# M221X.net
KiCad netlist of a schematic drawn in EAGLE
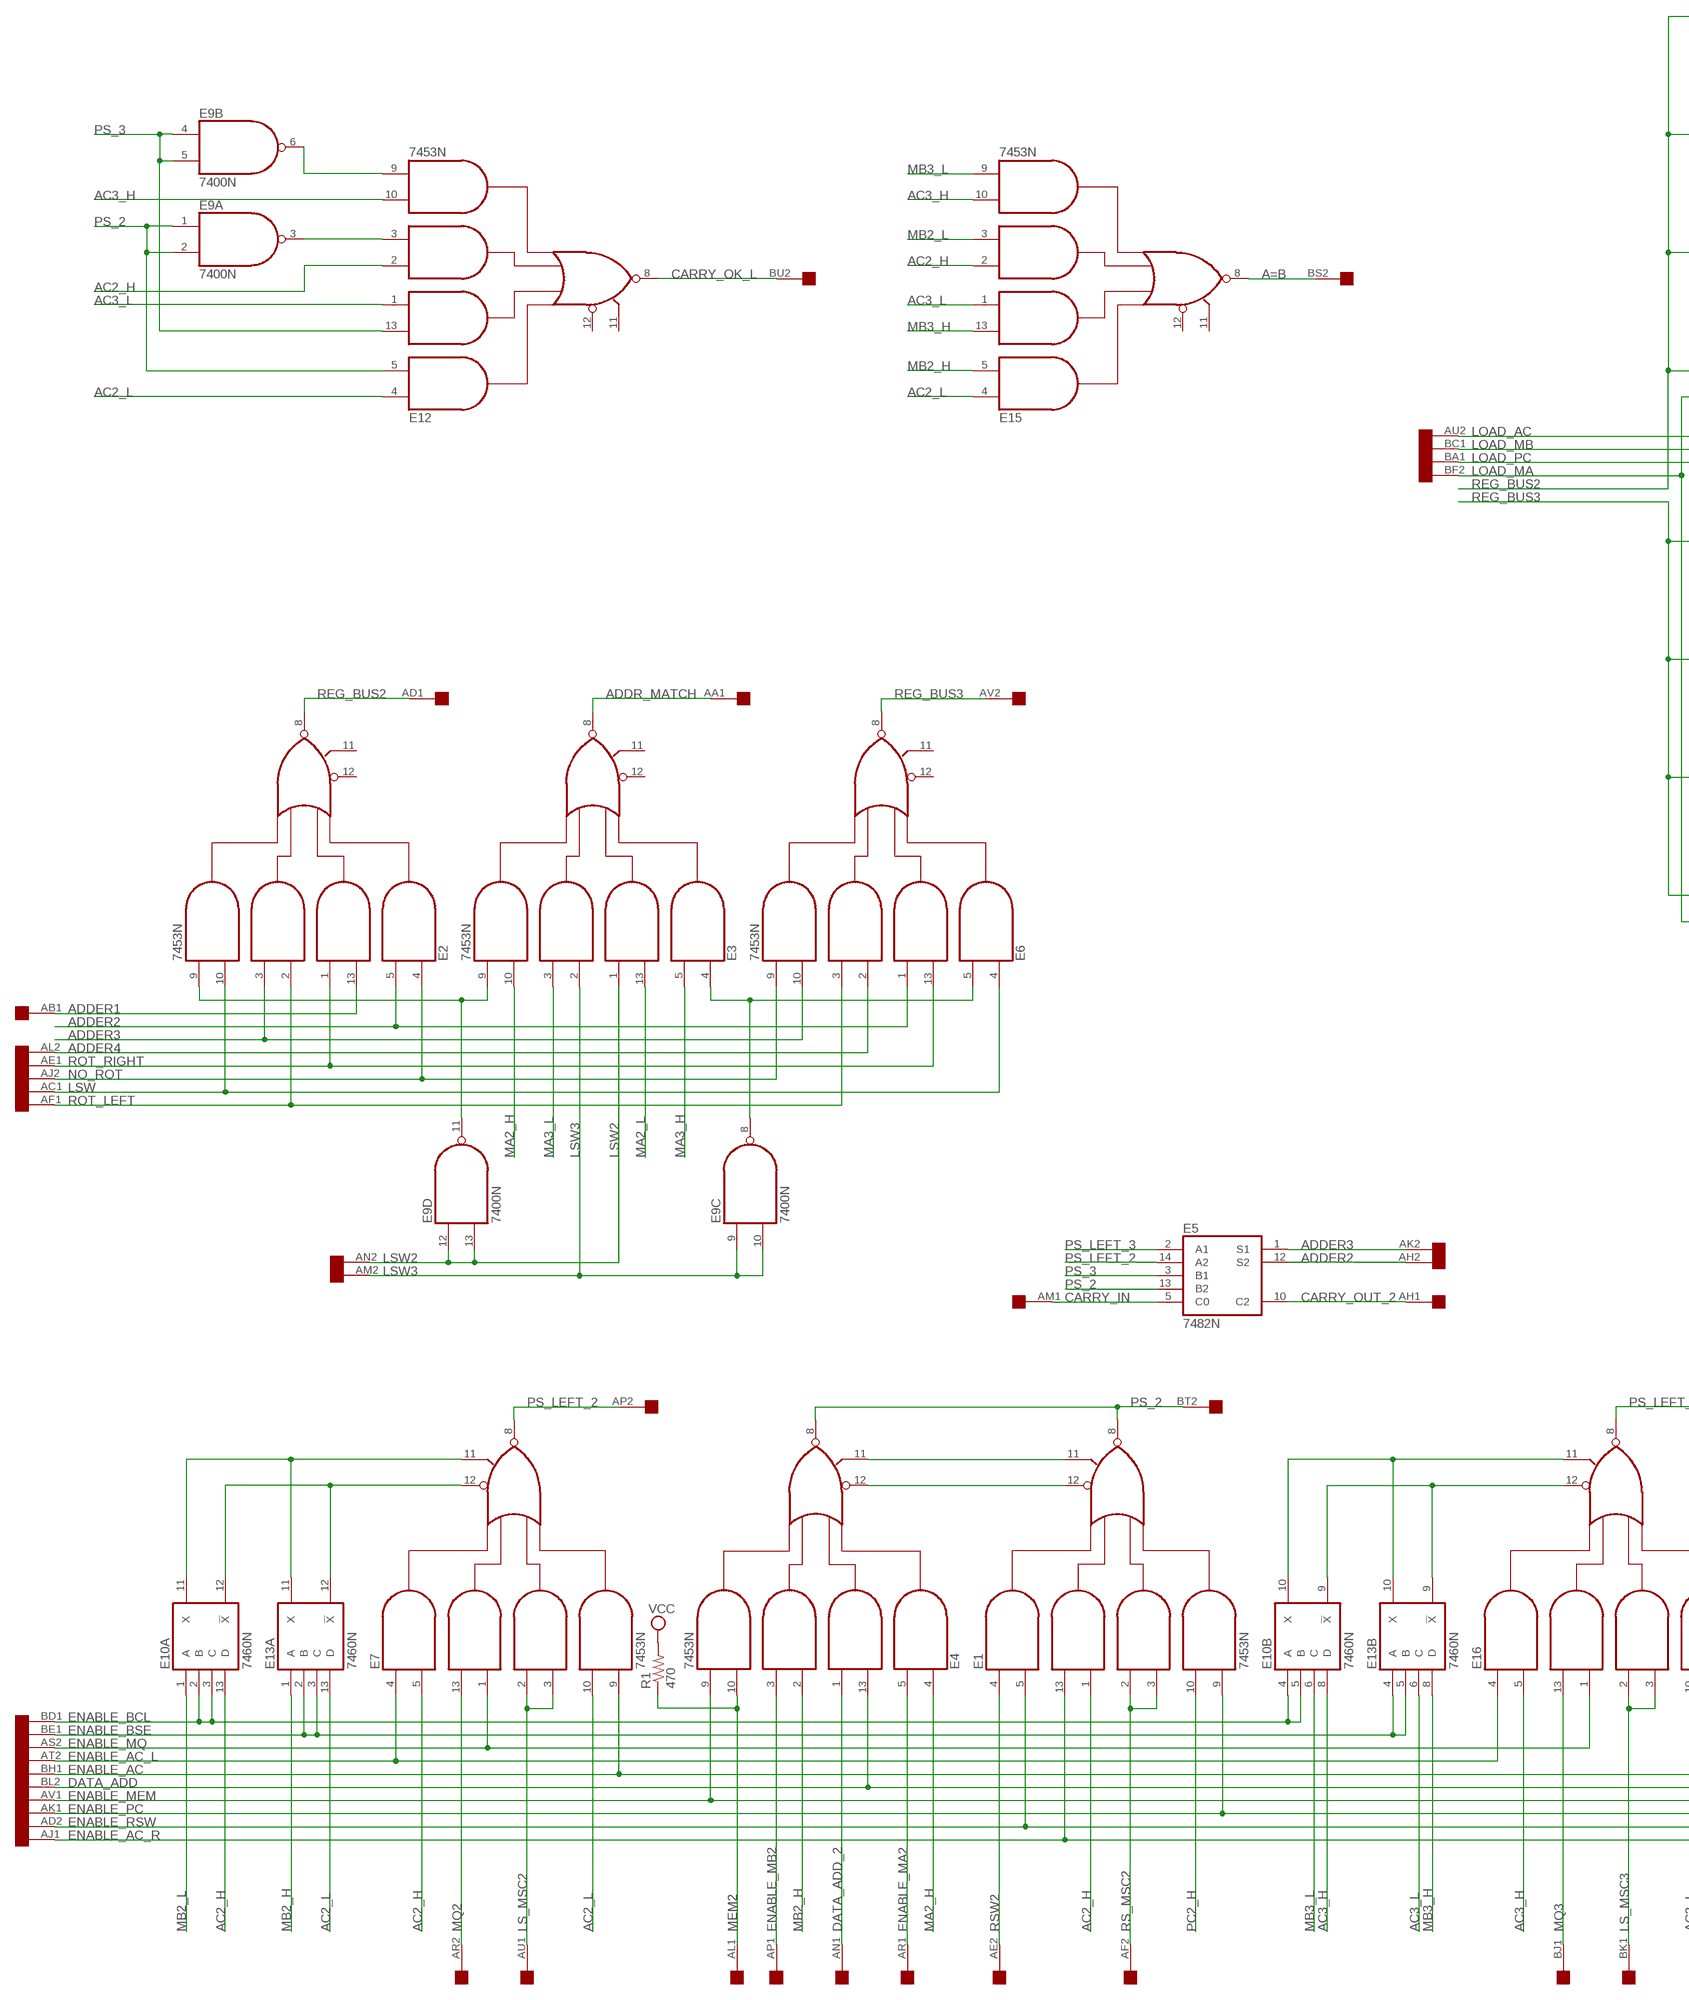
[diagram p0: schematic, sheet 1, part 1 of 2]
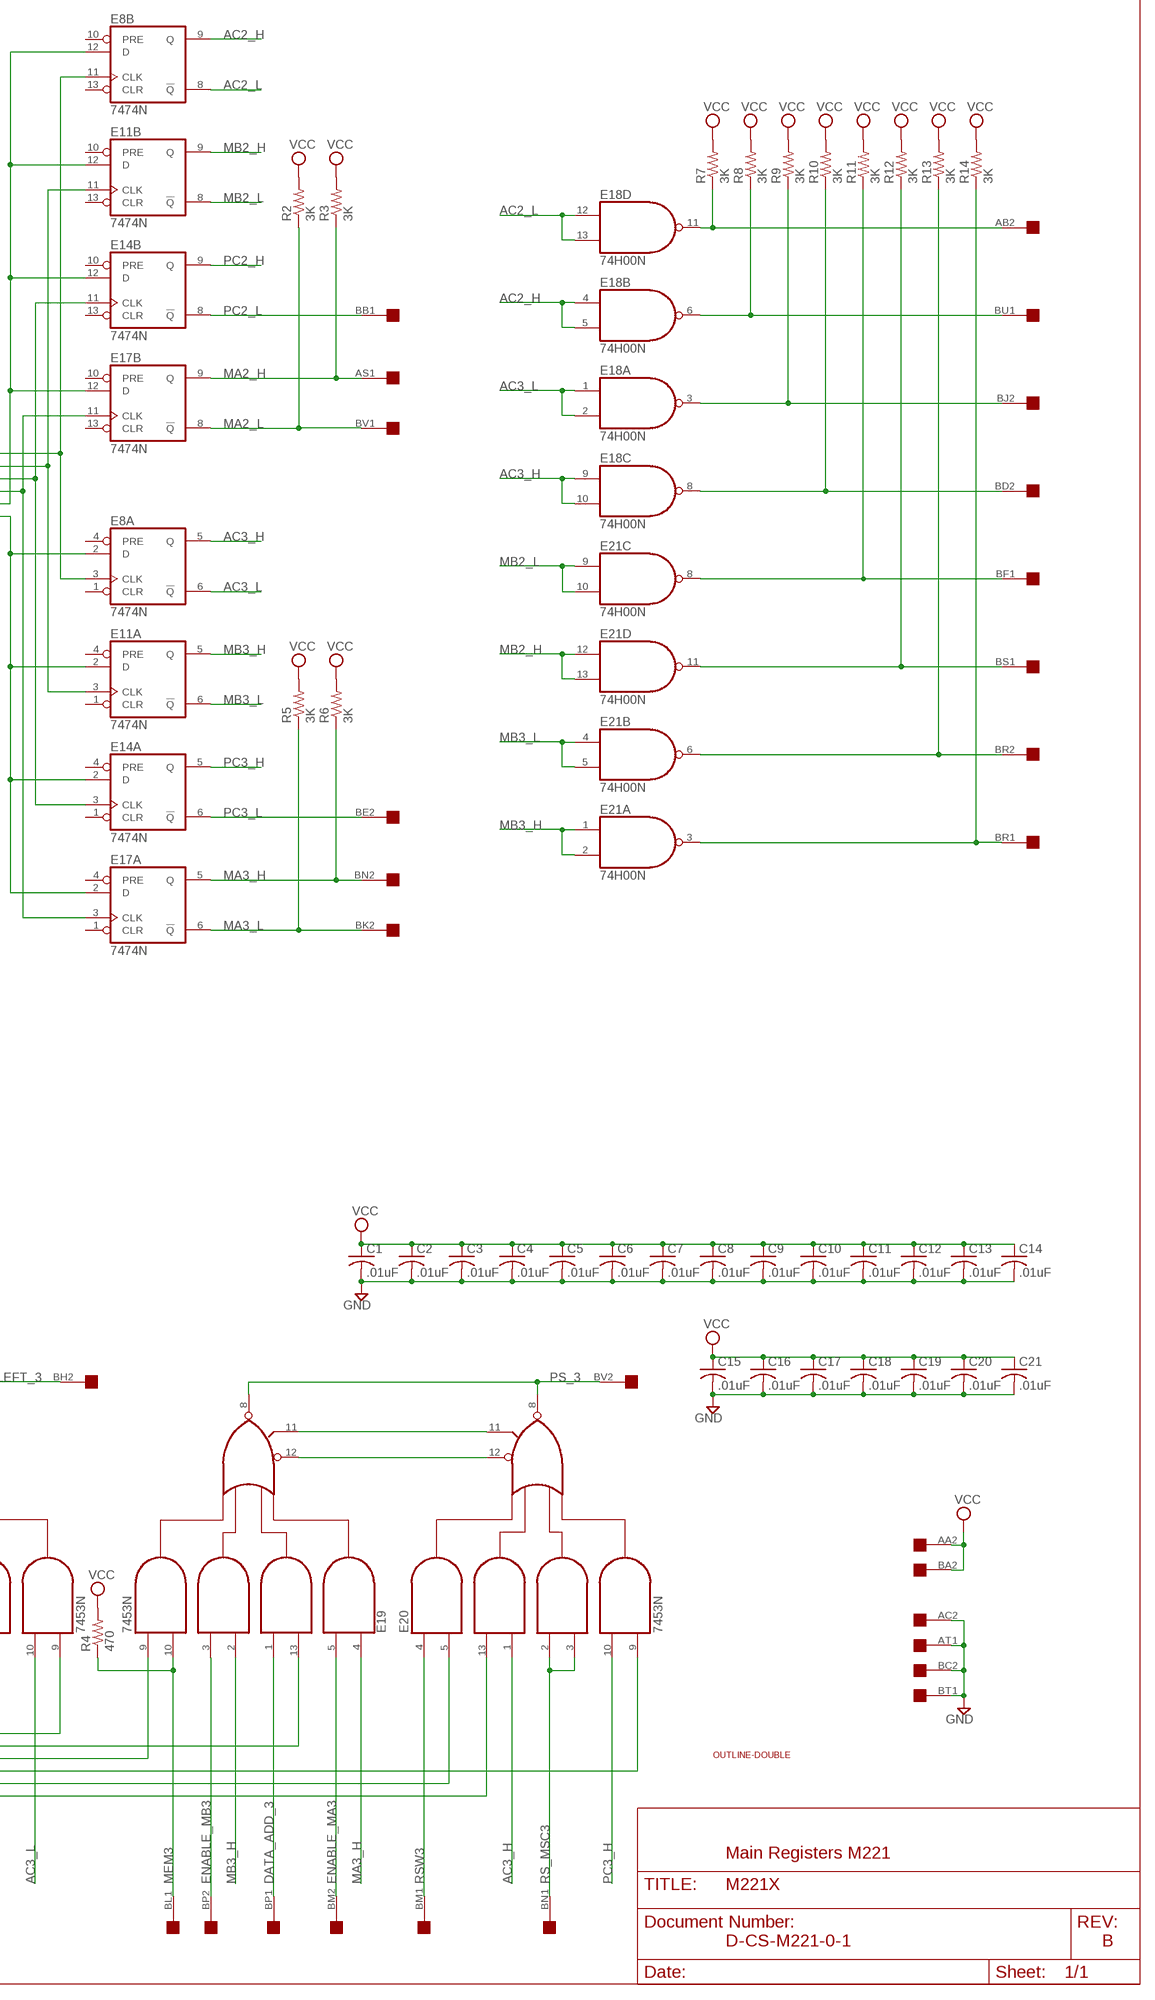
[diagram p1: schematic, sheet 1, part 2 of 2]

(export (version "E")
  (design (tool "Eeschema 10.0.6"))
  (components
    (comp (ref "C1")
      (value ".01uF")
      (footprint "eagle-import:C050-025X075")
      (libsource (lib "eagle-import") (part "C-US050-025X075"))
    )
    (comp (ref "C2")
      (value ".01uF")
      (footprint "eagle-import:C050-025X075")
      (libsource (lib "eagle-import") (part "C-US050-025X075"))
    )
    (comp (ref "C3")
      (value ".01uF")
      (footprint "eagle-import:C050-025X075")
      (libsource (lib "eagle-import") (part "C-US050-025X075"))
    )
    (comp (ref "C4")
      (value ".01uF")
      (footprint "eagle-import:C050-025X075")
      (libsource (lib "eagle-import") (part "C-US050-025X075"))
    )
    (comp (ref "C5")
      (value ".01uF")
      (footprint "eagle-import:C050-025X075")
      (libsource (lib "eagle-import") (part "C-US050-025X075"))
    )
    (comp (ref "C6")
      (value ".01uF")
      (footprint "eagle-import:C050-025X075")
      (libsource (lib "eagle-import") (part "C-US050-025X075"))
    )
    (comp (ref "C7")
      (value ".01uF")
      (footprint "eagle-import:C050-025X075")
      (libsource (lib "eagle-import") (part "C-US050-025X075"))
    )
    (comp (ref "C8")
      (value ".01uF")
      (footprint "eagle-import:C050-025X075")
      (libsource (lib "eagle-import") (part "C-US050-025X075"))
    )
    (comp (ref "C9")
      (value ".01uF")
      (footprint "eagle-import:C050-025X075")
      (libsource (lib "eagle-import") (part "C-US050-025X075"))
    )
    (comp (ref "C10")
      (value ".01uF")
      (footprint "eagle-import:C050-025X075")
      (libsource (lib "eagle-import") (part "C-US050-025X075"))
    )
    (comp (ref "C11")
      (value ".01uF")
      (footprint "eagle-import:C050-025X075")
      (libsource (lib "eagle-import") (part "C-US050-025X075"))
    )
    (comp (ref "C12")
      (value ".01uF")
      (footprint "eagle-import:C050-025X075")
      (libsource (lib "eagle-import") (part "C-US050-025X075"))
    )
    (comp (ref "C13")
      (value ".01uF")
      (footprint "eagle-import:C050-025X075")
      (libsource (lib "eagle-import") (part "C-US050-025X075"))
    )
    (comp (ref "C14")
      (value ".01uF")
      (footprint "eagle-import:C050-025X075")
      (libsource (lib "eagle-import") (part "C-US050-025X075"))
    )
    (comp (ref "C15")
      (value ".01uF")
      (footprint "eagle-import:C050-025X075")
      (libsource (lib "eagle-import") (part "C-US050-025X075"))
    )
    (comp (ref "C16")
      (value ".01uF")
      (footprint "eagle-import:C050-025X075")
      (libsource (lib "eagle-import") (part "C-US050-025X075"))
    )
    (comp (ref "C17")
      (value ".01uF")
      (footprint "eagle-import:C050-025X075")
      (libsource (lib "eagle-import") (part "C-US050-025X075"))
    )
    (comp (ref "C18")
      (value ".01uF")
      (footprint "eagle-import:C050-025X075")
      (libsource (lib "eagle-import") (part "C-US050-025X075"))
    )
    (comp (ref "C19")
      (value ".01uF")
      (footprint "eagle-import:C050-025X075")
      (libsource (lib "eagle-import") (part "C-US050-025X075"))
    )
    (comp (ref "C20")
      (value ".01uF")
      (footprint "eagle-import:C050-025X075")
      (libsource (lib "eagle-import") (part "C-US050-025X075"))
    )
    (comp (ref "C21")
      (value ".01uF")
      (footprint "eagle-import:C050-025X075")
      (libsource (lib "eagle-import") (part "C-US050-025X075"))
    )
    (comp (ref "E1")
      (value "7453N")
      (footprint "eagle-import:DIL14")
      (libsource (lib "eagle-import") (part "7453N"))
    )
    (comp (ref "E2")
      (value "7453N")
      (footprint "eagle-import:DIL14")
      (libsource (lib "eagle-import") (part "7453N"))
    )
    (comp (ref "E3")
      (value "7453N")
      (footprint "eagle-import:DIL14")
      (libsource (lib "eagle-import") (part "7453N"))
    )
    (comp (ref "E4")
      (value "7453N")
      (footprint "eagle-import:DIL14")
      (libsource (lib "eagle-import") (part "7453N"))
    )
    (comp (ref "E5")
      (value "7482N")
      (footprint "eagle-import:DIL14")
      (libsource (lib "eagle-import") (part "7482N"))
    )
    (comp (ref "E6")
      (value "7453N")
      (footprint "eagle-import:DIL14")
      (libsource (lib "eagle-import") (part "7453N"))
    )
    (comp (ref "E7")
      (value "7453N")
      (footprint "eagle-import:DIL14")
      (libsource (lib "eagle-import") (part "7453N"))
    )
    (comp (ref "E8")
      (value "7474N")
      (footprint "eagle-import:DIL14")
      (libsource (lib "eagle-import") (part "7474NS"))
    )
    (comp (ref "E9")
      (value "7400N")
      (footprint "eagle-import:DIL14")
      (libsource (lib "eagle-import") (part "7400N"))
    )
    (comp (ref "E10")
      (value "7460N")
      (footprint "eagle-import:DIL14")
      (libsource (lib "eagle-import") (part "7460N"))
    )
    (comp (ref "E11")
      (value "7474N")
      (footprint "eagle-import:DIL14")
      (libsource (lib "eagle-import") (part "7474NS"))
    )
    (comp (ref "E12")
      (value "7453N")
      (footprint "eagle-import:DIL14")
      (libsource (lib "eagle-import") (part "7453N"))
    )
    (comp (ref "E13")
      (value "7460N")
      (footprint "eagle-import:DIL14")
      (libsource (lib "eagle-import") (part "7460N"))
    )
    (comp (ref "E14")
      (value "7474N")
      (footprint "eagle-import:DIL14")
      (libsource (lib "eagle-import") (part "7474NS"))
    )
    (comp (ref "E15")
      (value "7453N")
      (footprint "eagle-import:DIL14")
      (libsource (lib "eagle-import") (part "7453N"))
    )
    (comp (ref "E16")
      (value "7453N")
      (footprint "eagle-import:DIL14")
      (libsource (lib "eagle-import") (part "7453N"))
    )
    (comp (ref "E17")
      (value "7474N")
      (footprint "eagle-import:DIL14")
      (libsource (lib "eagle-import") (part "7474NS"))
    )
    (comp (ref "E18")
      (value "74H00N")
      (footprint "eagle-import:DIL14")
      (libsource (lib "eagle-import") (part "7400N"))
    )
    (comp (ref "E19")
      (value "7453N")
      (footprint "eagle-import:DIL14")
      (libsource (lib "eagle-import") (part "7453N"))
    )
    (comp (ref "E20")
      (value "7453N")
      (footprint "eagle-import:DIL14")
      (libsource (lib "eagle-import") (part "7453N"))
    )
    (comp (ref "E21")
      (value "74H00N")
      (footprint "eagle-import:DIL14")
      (libsource (lib "eagle-import") (part "7400N"))
    )
    (comp (ref "R1")
      (value "470")
      (footprint "eagle-import:0207_10")
      (libsource (lib "eagle-import") (part "R-US_0207/10"))
    )
    (comp (ref "R2")
      (value "3K")
      (footprint "eagle-import:0207_10")
      (libsource (lib "eagle-import") (part "R-US_0207/10"))
    )
    (comp (ref "R3")
      (value "3K")
      (footprint "eagle-import:0207_10")
      (libsource (lib "eagle-import") (part "R-US_0207/10"))
    )
    (comp (ref "R4")
      (value "470")
      (footprint "eagle-import:0207_10")
      (libsource (lib "eagle-import") (part "R-US_0207/10"))
    )
    (comp (ref "R5")
      (value "3K")
      (footprint "eagle-import:0207_10")
      (libsource (lib "eagle-import") (part "R-US_0207/10"))
    )
    (comp (ref "R6")
      (value "3K")
      (footprint "eagle-import:0207_10")
      (libsource (lib "eagle-import") (part "R-US_0207/10"))
    )
    (comp (ref "R7")
      (value "3K")
      (footprint "eagle-import:0207_10")
      (libsource (lib "eagle-import") (part "R-US_0207/10"))
    )
    (comp (ref "R8")
      (value "3K")
      (footprint "eagle-import:0207_10")
      (libsource (lib "eagle-import") (part "R-US_0207/10"))
    )
    (comp (ref "R9")
      (value "3K")
      (footprint "eagle-import:0207_10")
      (libsource (lib "eagle-import") (part "R-US_0207/10"))
    )
    (comp (ref "R10")
      (value "3K")
      (footprint "eagle-import:0207_10")
      (libsource (lib "eagle-import") (part "R-US_0207/10"))
    )
    (comp (ref "R11")
      (value "3K")
      (footprint "eagle-import:0207_10")
      (libsource (lib "eagle-import") (part "R-US_0207/10"))
    )
    (comp (ref "R12")
      (value "3K")
      (footprint "eagle-import:0207_10")
      (libsource (lib "eagle-import") (part "R-US_0207/10"))
    )
    (comp (ref "R13")
      (value "3K")
      (footprint "eagle-import:0207_10")
      (libsource (lib "eagle-import") (part "R-US_0207/10"))
    )
    (comp (ref "R14")
      (value "3K")
      (footprint "eagle-import:0207_10")
      (libsource (lib "eagle-import") (part "R-US_0207/10"))
    )
    (comp (ref "U$1")
      (value "DOUBLE")
      (footprint "eagle-import:EDGE-CON4")
      (libsource (lib "eagle-import") (part "DOUBLE"))
    )
    (comp (ref "U$2")
      (value "OUTLINE-DOUBLE")
      (footprint "eagle-import:DOUBLE")
      (libsource (lib "eagle-import") (part "OUTLINE-DOUBLE"))
    )
  )
  (nets
    (net (code "1") (name "/A=B") (class "Default")
      (node (ref "E15") (pin "8") (pinfunction "O_8") (pintype "output"))
      (node (ref "U$1") (pin "BS2") (pinfunction "1_BS2") (pintype "bidirectional"))
    )
    (net (code "2") (name "/AC2_H") (class "Default")
      (node (ref "E1") (pin "1") (pinfunction "I4_1") (pintype "input"))
      (node (ref "E10") (pin "13") (pinfunction "D_13") (pintype "input"))
      (node (ref "E12") (pin "2") (pinfunction "I5_2") (pintype "input"))
      (node (ref "E15") (pin "2") (pinfunction "I5_2") (pintype "input"))
      (node (ref "E18") (pin "4") (pinfunction "I0_4") (pintype "input"))
      (node (ref "E18") (pin "5") (pinfunction "I1_5") (pintype "input"))
      (node (ref "E7") (pin "5") (pinfunction "I2_5") (pintype "input"))
      (node (ref "E8") (pin "9") (pinfunction "Q_9") (pintype "output"))
    )
    (net (code "3") (name "/AC2_L") (class "Default")
      (node (ref "E12") (pin "4") (pinfunction "I1_4") (pintype "input"))
      (node (ref "E13") (pin "13") (pinfunction "D_13") (pintype "input"))
      (node (ref "E15") (pin "4") (pinfunction "I1_4") (pintype "input"))
      (node (ref "E18") (pin "12") (pinfunction "I0_12") (pintype "input"))
      (node (ref "E18") (pin "13") (pinfunction "I1_13") (pintype "input"))
      (node (ref "E7") (pin "10") (pinfunction "I7_10") (pintype "input"))
      (node (ref "E8") (pin "8") (pinfunction "~{Q}_8") (pintype "output"))
    )
    (net (code "4") (name "/AC3_H") (class "Default")
      (node (ref "E10") (pin "8") (pinfunction "D_8") (pintype "input"))
      (node (ref "E12") (pin "10") (pinfunction "I7_10") (pintype "input"))
      (node (ref "E15") (pin "10") (pinfunction "I7_10") (pintype "input"))
      (node (ref "E16") (pin "5") (pinfunction "I2_5") (pintype "input"))
      (node (ref "E18") (pin "10") (pinfunction "I1_10") (pintype "input"))
      (node (ref "E18") (pin "9") (pinfunction "I0_9") (pintype "input"))
      (node (ref "E20") (pin "1") (pinfunction "I4_1") (pintype "input"))
      (node (ref "E8") (pin "5") (pinfunction "Q_5") (pintype "output"))
    )
    (net (code "5") (name "/AC3_L") (class "Default")
      (node (ref "E12") (pin "1") (pinfunction "I4_1") (pintype "input"))
      (node (ref "E13") (pin "6") (pinfunction "C_6") (pintype "input"))
      (node (ref "E15") (pin "1") (pinfunction "I4_1") (pintype "input"))
      (node (ref "E16") (pin "10") (pinfunction "I7_10") (pintype "input"))
      (node (ref "E18") (pin "1") (pinfunction "I0_1") (pintype "input"))
      (node (ref "E18") (pin "2") (pinfunction "I1_2") (pintype "input"))
      (node (ref "E8") (pin "6") (pinfunction "~{Q}_6") (pintype "output"))
    )
    (net (code "6") (name "/ADDER1") (class "Default")
      (node (ref "E2") (pin "13") (pinfunction "I3_13") (pintype "input"))
      (node (ref "U$1") (pin "AB1") (pinfunction "1_AB1") (pintype "bidirectional"))
    )
    (net (code "7") (name "/ADDER2") (class "Default")
      (node (ref "E2") (pin "5") (pinfunction "I2_5") (pintype "input"))
      (node (ref "E5") (pin "12") (pinfunction "S2_12") (pintype "output"))
      (node (ref "E6") (pin "1") (pinfunction "I4_1") (pintype "input"))
      (node (ref "U$1") (pin "AH2") (pinfunction "1_AH2") (pintype "bidirectional"))
    )
    (net (code "8") (name "/ADDER3") (class "Default")
      (node (ref "E2") (pin "3") (pinfunction "I6_3") (pintype "input"))
      (node (ref "E5") (pin "1") (pinfunction "S1_1") (pintype "output"))
      (node (ref "E6") (pin "10") (pinfunction "I7_10") (pintype "input"))
      (node (ref "U$1") (pin "AK2") (pinfunction "1_AK2") (pintype "bidirectional"))
    )
    (net (code "9") (name "/ADDER4") (class "Default")
      (node (ref "E6") (pin "2") (pinfunction "I5_2") (pintype "input"))
      (node (ref "U$1") (pin "AL2") (pinfunction "1_AL2") (pintype "bidirectional"))
    )
    (net (code "10") (name "/ADDR_MATCH") (class "Default")
      (node (ref "E3") (pin "8") (pinfunction "O_8") (pintype "output"))
      (node (ref "U$1") (pin "AA1") (pinfunction "1_AA1") (pintype "bidirectional"))
    )
    (net (code "11") (name "/CARRY_IN") (class "Default")
      (node (ref "E5") (pin "5") (pinfunction "C0_5") (pintype "input"))
      (node (ref "U$1") (pin "AM1") (pinfunction "1_AM1") (pintype "bidirectional"))
    )
    (net (code "12") (name "/CARRY_OK_L") (class "Default")
      (node (ref "E12") (pin "8") (pinfunction "O_8") (pintype "output"))
      (node (ref "U$1") (pin "BU2") (pinfunction "1_BU2") (pintype "bidirectional"))
    )
    (net (code "13") (name "/CARRY_OUT_2") (class "Default")
      (node (ref "E5") (pin "10") (pinfunction "C2_10") (pintype "output"))
      (node (ref "U$1") (pin "AH1") (pinfunction "1_AH1") (pintype "bidirectional"))
    )
    (net (code "14") (name "/DATA_ADD") (class "Default")
      (node (ref "E19") (pin "13") (pinfunction "I3_13") (pintype "input"))
      (node (ref "E4") (pin "13") (pinfunction "I3_13") (pintype "input"))
      (node (ref "U$1") (pin "BL2") (pinfunction "1_BL2") (pintype "bidirectional"))
    )
    (net (code "15") (name "/DATA_ADD_2") (class "Default")
      (node (ref "E4") (pin "1") (pinfunction "I4_1") (pintype "input"))
      (node (ref "U$1") (pin "AN1") (pinfunction "1_AN1") (pintype "bidirectional"))
    )
    (net (code "16") (name "/DATA_ADD_3") (class "Default")
      (node (ref "E19") (pin "1") (pinfunction "I4_1") (pintype "input"))
      (node (ref "U$1") (pin "BP1") (pinfunction "1_BP1") (pintype "bidirectional"))
    )
    (net (code "17") (name "/ENABLE_AC") (class "Default")
      (node (ref "E16") (pin "9") (pinfunction "I8_9") (pintype "input"))
      (node (ref "E7") (pin "9") (pinfunction "I8_9") (pintype "input"))
      (node (ref "U$1") (pin "BH1") (pinfunction "1_BH1") (pintype "bidirectional"))
    )
    (net (code "18") (name "/ENABLE_AC_L") (class "Default")
      (node (ref "E16") (pin "4") (pinfunction "I1_4") (pintype "input"))
      (node (ref "E7") (pin "4") (pinfunction "I1_4") (pintype "input"))
      (node (ref "U$1") (pin "AT2") (pinfunction "1_AT2") (pintype "bidirectional"))
    )
    (net (code "19") (name "/ENABLE_AC_R") (class "Default")
      (node (ref "E1") (pin "13") (pinfunction "I3_13") (pintype "input"))
      (node (ref "E20") (pin "13") (pinfunction "I3_13") (pintype "input"))
      (node (ref "U$1") (pin "AJ1") (pinfunction "1_AJ1") (pintype "bidirectional"))
    )
    (net (code "20") (name "/ENABLE_BCL") (class "Default")
      (node (ref "E10") (pin "2") (pinfunction "B_2") (pintype "input"))
      (node (ref "E10") (pin "3") (pinfunction "C_3") (pintype "input"))
      (node (ref "E10") (pin "4") (pinfunction "A_4") (pintype "input"))
      (node (ref "E10") (pin "5") (pinfunction "B_5") (pintype "input"))
      (node (ref "U$1") (pin "BD1") (pinfunction "1_BD1") (pintype "bidirectional"))
    )
    (net (code "21") (name "/ENABLE_BSE") (class "Default")
      (node (ref "E13") (pin "2") (pinfunction "B_2") (pintype "input"))
      (node (ref "E13") (pin "3") (pinfunction "C_3") (pintype "input"))
      (node (ref "E13") (pin "4") (pinfunction "A_4") (pintype "input"))
      (node (ref "E13") (pin "5") (pinfunction "B_5") (pintype "input"))
      (node (ref "U$1") (pin "BE1") (pinfunction "1_BE1") (pintype "bidirectional"))
    )
    (net (code "22") (name "/ENABLE_MA2") (class "Default")
      (node (ref "E4") (pin "5") (pinfunction "I2_5") (pintype "input"))
      (node (ref "U$1") (pin "AR1") (pinfunction "1_AR1") (pintype "bidirectional"))
    )
    (net (code "23") (name "/ENABLE_MA3") (class "Default")
      (node (ref "E19") (pin "5") (pinfunction "I2_5") (pintype "input"))
      (node (ref "U$1") (pin "BM2") (pinfunction "1_BM2") (pintype "bidirectional"))
    )
    (net (code "24") (name "/ENABLE_MB2") (class "Default")
      (node (ref "E4") (pin "3") (pinfunction "I6_3") (pintype "input"))
      (node (ref "U$1") (pin "AP1") (pinfunction "1_AP1") (pintype "bidirectional"))
    )
    (net (code "25") (name "/ENABLE_MB3") (class "Default")
      (node (ref "E19") (pin "3") (pinfunction "I6_3") (pintype "input"))
      (node (ref "U$1") (pin "BP2") (pinfunction "1_BP2") (pintype "bidirectional"))
    )
    (net (code "26") (name "/ENABLE_MEM") (class "Default")
      (node (ref "E19") (pin "9") (pinfunction "I8_9") (pintype "input"))
      (node (ref "E4") (pin "9") (pinfunction "I8_9") (pintype "input"))
      (node (ref "U$1") (pin "AV1") (pinfunction "1_AV1") (pintype "bidirectional"))
    )
    (net (code "27") (name "/ENABLE_MQ") (class "Default")
      (node (ref "E16") (pin "1") (pinfunction "I4_1") (pintype "input"))
      (node (ref "E7") (pin "1") (pinfunction "I4_1") (pintype "input"))
      (node (ref "U$1") (pin "AS2") (pinfunction "1_AS2") (pintype "bidirectional"))
    )
    (net (code "28") (name "/ENABLE_PC") (class "Default")
      (node (ref "E1") (pin "9") (pinfunction "I8_9") (pintype "input"))
      (node (ref "E20") (pin "9") (pinfunction "I8_9") (pintype "input"))
      (node (ref "U$1") (pin "AK1") (pinfunction "1_AK1") (pintype "bidirectional"))
    )
    (net (code "29") (name "/ENABLE_RSW") (class "Default")
      (node (ref "E1") (pin "5") (pinfunction "I2_5") (pintype "input"))
      (node (ref "E20") (pin "5") (pinfunction "I2_5") (pintype "input"))
      (node (ref "U$1") (pin "AD2") (pinfunction "1_AD2") (pintype "bidirectional"))
    )
    (net (code "30") (name "/LOAD_AC") (class "Default")
      (node (ref "E8") (pin "11") (pinfunction "CLK_11") (pintype "input"))
      (node (ref "E8") (pin "3") (pinfunction "CLK_3") (pintype "input"))
      (node (ref "U$1") (pin "AU2") (pinfunction "1_AU2") (pintype "bidirectional"))
    )
    (net (code "31") (name "/LOAD_MA") (class "Default")
      (node (ref "E17") (pin "11") (pinfunction "CLK_11") (pintype "input"))
      (node (ref "E17") (pin "3") (pinfunction "CLK_3") (pintype "input"))
      (node (ref "U$1") (pin "BF2") (pinfunction "1_BF2") (pintype "bidirectional"))
    )
    (net (code "32") (name "/LOAD_MB") (class "Default")
      (node (ref "E11") (pin "11") (pinfunction "CLK_11") (pintype "input"))
      (node (ref "E11") (pin "3") (pinfunction "CLK_3") (pintype "input"))
      (node (ref "U$1") (pin "BC1") (pinfunction "1_BC1") (pintype "bidirectional"))
    )
    (net (code "33") (name "/LOAD_PC") (class "Default")
      (node (ref "E14") (pin "11") (pinfunction "CLK_11") (pintype "input"))
      (node (ref "E14") (pin "3") (pinfunction "CLK_3") (pintype "input"))
      (node (ref "U$1") (pin "BA1") (pinfunction "1_BA1") (pintype "bidirectional"))
    )
    (net (code "34") (name "/LSW") (class "Default")
      (node (ref "E2") (pin "10") (pinfunction "I7_10") (pintype "input"))
      (node (ref "E6") (pin "4") (pinfunction "I1_4") (pintype "input"))
      (node (ref "U$1") (pin "AC1") (pinfunction "1_AC1") (pintype "bidirectional"))
    )
    (net (code "35") (name "/LSW2") (class "Default")
      (node (ref "E3") (pin "1") (pinfunction "I4_1") (pintype "input"))
      (node (ref "E9") (pin "12") (pinfunction "I0_12") (pintype "input"))
      (node (ref "E9") (pin "13") (pinfunction "I1_13") (pintype "input"))
      (node (ref "U$1") (pin "AN2") (pinfunction "1_AN2") (pintype "bidirectional"))
    )
    (net (code "36") (name "/LSW3") (class "Default")
      (node (ref "E3") (pin "2") (pinfunction "I5_2") (pintype "input"))
      (node (ref "E9") (pin "10") (pinfunction "I1_10") (pintype "input"))
      (node (ref "E9") (pin "9") (pinfunction "I0_9") (pintype "input"))
      (node (ref "U$1") (pin "AM2") (pinfunction "1_AM2") (pintype "bidirectional"))
    )
    (net (code "37") (name "/LS_MSC2") (class "Default")
      (node (ref "E7") (pin "2") (pinfunction "I5_2") (pintype "input"))
      (node (ref "E7") (pin "3") (pinfunction "I6_3") (pintype "input"))
      (node (ref "U$1") (pin "AU1") (pinfunction "1_AU1") (pintype "bidirectional"))
    )
    (net (code "38") (name "/LS_MSC3") (class "Default")
      (node (ref "E16") (pin "2") (pinfunction "I5_2") (pintype "input"))
      (node (ref "E16") (pin "3") (pinfunction "I6_3") (pintype "input"))
      (node (ref "U$1") (pin "BK1") (pinfunction "1_BK1") (pintype "bidirectional"))
    )
    (net (code "39") (name "/MA2_H") (class "Default")
      (node (ref "E17") (pin "9") (pinfunction "Q_9") (pintype "output"))
      (node (ref "E3") (pin "10") (pinfunction "I7_10") (pintype "input"))
      (node (ref "E4") (pin "4") (pinfunction "I1_4") (pintype "input"))
      (node (ref "R3") (pin "1") (pinfunction "1_1") (pintype "passive"))
      (node (ref "U$1") (pin "AS1") (pinfunction "1_AS1") (pintype "bidirectional"))
    )
    (net (code "40") (name "/MA2_L") (class "Default")
      (node (ref "E17") (pin "8") (pinfunction "~{Q}_8") (pintype "output"))
      (node (ref "E3") (pin "13") (pinfunction "I3_13") (pintype "input"))
      (node (ref "R2") (pin "1") (pinfunction "1_1") (pintype "passive"))
      (node (ref "U$1") (pin "BV1") (pinfunction "1_BV1") (pintype "bidirectional"))
    )
    (net (code "41") (name "/MA3_H") (class "Default")
      (node (ref "E17") (pin "5") (pinfunction "Q_5") (pintype "output"))
      (node (ref "E19") (pin "4") (pinfunction "I1_4") (pintype "input"))
      (node (ref "E3") (pin "5") (pinfunction "I2_5") (pintype "input"))
      (node (ref "R6") (pin "1") (pinfunction "1_1") (pintype "passive"))
      (node (ref "U$1") (pin "BN2") (pinfunction "1_BN2") (pintype "bidirectional"))
    )
    (net (code "42") (name "/MA3_L") (class "Default")
      (node (ref "E17") (pin "6") (pinfunction "~{Q}_6") (pintype "output"))
      (node (ref "E3") (pin "3") (pinfunction "I6_3") (pintype "input"))
      (node (ref "R5") (pin "1") (pinfunction "1_1") (pintype "passive"))
      (node (ref "U$1") (pin "BK2") (pinfunction "1_BK2") (pintype "bidirectional"))
    )
    (net (code "43") (name "/MB2_H") (class "Default")
      (node (ref "E11") (pin "9") (pinfunction "Q_9") (pintype "output"))
      (node (ref "E13") (pin "1") (pinfunction "A_1") (pintype "input"))
      (node (ref "E15") (pin "5") (pinfunction "I2_5") (pintype "input"))
      (node (ref "E21") (pin "12") (pinfunction "I0_12") (pintype "input"))
      (node (ref "E21") (pin "13") (pinfunction "I1_13") (pintype "input"))
      (node (ref "E4") (pin "2") (pinfunction "I5_2") (pintype "input"))
    )
    (net (code "44") (name "/MB2_L") (class "Default")
      (node (ref "E10") (pin "1") (pinfunction "A_1") (pintype "input"))
      (node (ref "E11") (pin "8") (pinfunction "~{Q}_8") (pintype "output"))
      (node (ref "E15") (pin "3") (pinfunction "I6_3") (pintype "input"))
      (node (ref "E21") (pin "10") (pinfunction "I1_10") (pintype "input"))
      (node (ref "E21") (pin "9") (pinfunction "I0_9") (pintype "input"))
    )
    (net (code "45") (name "/MB3_H") (class "Default")
      (node (ref "E11") (pin "5") (pinfunction "Q_5") (pintype "output"))
      (node (ref "E13") (pin "8") (pinfunction "D_8") (pintype "input"))
      (node (ref "E15") (pin "13") (pinfunction "I3_13") (pintype "input"))
      (node (ref "E19") (pin "2") (pinfunction "I5_2") (pintype "input"))
      (node (ref "E21") (pin "1") (pinfunction "I0_1") (pintype "input"))
      (node (ref "E21") (pin "2") (pinfunction "I1_2") (pintype "input"))
    )
    (net (code "46") (name "/MB3_L") (class "Default")
      (node (ref "E10") (pin "6") (pinfunction "C_6") (pintype "input"))
      (node (ref "E11") (pin "6") (pinfunction "~{Q}_6") (pintype "output"))
      (node (ref "E15") (pin "9") (pinfunction "I8_9") (pintype "input"))
      (node (ref "E21") (pin "4") (pinfunction "I0_4") (pintype "input"))
      (node (ref "E21") (pin "5") (pinfunction "I1_5") (pintype "input"))
    )
    (net (code "47") (name "/MEM2") (class "Default")
      (node (ref "E4") (pin "10") (pinfunction "I7_10") (pintype "input"))
      (node (ref "R1") (pin "1") (pinfunction "1_1") (pintype "passive"))
      (node (ref "U$1") (pin "AL1") (pinfunction "1_AL1") (pintype "bidirectional"))
    )
    (net (code "48") (name "/MEM3") (class "Default")
      (node (ref "E19") (pin "10") (pinfunction "I7_10") (pintype "input"))
      (node (ref "R4") (pin "1") (pinfunction "1_1") (pintype "passive"))
      (node (ref "U$1") (pin "BL1") (pinfunction "1_BL1") (pintype "bidirectional"))
    )
    (net (code "49") (name "/MQ2") (class "Default")
      (node (ref "E7") (pin "13") (pinfunction "I3_13") (pintype "input"))
      (node (ref "U$1") (pin "AR2") (pinfunction "1_AR2") (pintype "bidirectional"))
    )
    (net (code "50") (name "/MQ3") (class "Default")
      (node (ref "E16") (pin "13") (pinfunction "I3_13") (pintype "input"))
      (node (ref "U$1") (pin "BJ1") (pinfunction "1_BJ1") (pintype "bidirectional"))
    )
    (net (code "51") (name "/NO_ROT") (class "Default")
      (node (ref "E2") (pin "4") (pinfunction "I1_4") (pintype "input"))
      (node (ref "E6") (pin "9") (pinfunction "I8_9") (pintype "input"))
      (node (ref "U$1") (pin "AJ2") (pinfunction "1_AJ2") (pintype "bidirectional"))
    )
    (net (code "52") (name "/PC2_H") (class "Default")
      (node (ref "E1") (pin "10") (pinfunction "I7_10") (pintype "input"))
      (node (ref "E14") (pin "9") (pinfunction "Q_9") (pintype "output"))
    )
    (net (code "53") (name "/PC2_L") (class "Default")
      (node (ref "E14") (pin "8") (pinfunction "~{Q}_8") (pintype "output"))
      (node (ref "U$1") (pin "BB1") (pinfunction "1_BB1") (pintype "bidirectional"))
    )
    (net (code "54") (name "/PC3_H") (class "Default")
      (node (ref "E14") (pin "5") (pinfunction "Q_5") (pintype "output"))
      (node (ref "E20") (pin "10") (pinfunction "I7_10") (pintype "input"))
    )
    (net (code "55") (name "/PC3_L") (class "Default")
      (node (ref "E14") (pin "6") (pinfunction "~{Q}_6") (pintype "output"))
      (node (ref "U$1") (pin "BE2") (pinfunction "1_BE2") (pintype "bidirectional"))
    )
    (net (code "56") (name "/PS_2") (class "Default")
      (node (ref "E1") (pin "8") (pinfunction "O_8") (pintype "output"))
      (node (ref "E12") (pin "5") (pinfunction "I2_5") (pintype "input"))
      (node (ref "E4") (pin "8") (pinfunction "O_8") (pintype "output"))
      (node (ref "E5") (pin "13") (pinfunction "B2_13") (pintype "input"))
      (node (ref "E9") (pin "1") (pinfunction "I0_1") (pintype "input"))
      (node (ref "E9") (pin "2") (pinfunction "I1_2") (pintype "input"))
      (node (ref "U$1") (pin "BT2") (pinfunction "1_BT2") (pintype "bidirectional"))
    )
    (net (code "57") (name "/PS_3") (class "Default")
      (node (ref "E12") (pin "13") (pinfunction "I3_13") (pintype "input"))
      (node (ref "E19") (pin "8") (pinfunction "O_8") (pintype "output"))
      (node (ref "E20") (pin "8") (pinfunction "O_8") (pintype "output"))
      (node (ref "E5") (pin "3") (pinfunction "B1_3") (pintype "input"))
      (node (ref "E9") (pin "4") (pinfunction "I0_4") (pintype "input"))
      (node (ref "E9") (pin "5") (pinfunction "I1_5") (pintype "input"))
      (node (ref "U$1") (pin "BV2") (pinfunction "1_BV2") (pintype "bidirectional"))
    )
    (net (code "58") (name "/PS_LEFT_2") (class "Default")
      (node (ref "E5") (pin "14") (pinfunction "A2_14") (pintype "input"))
      (node (ref "E7") (pin "8") (pinfunction "O_8") (pintype "output"))
      (node (ref "U$1") (pin "AP2") (pinfunction "1_AP2") (pintype "bidirectional"))
    )
    (net (code "59") (name "/PS_LEFT_3") (class "Default")
      (node (ref "E16") (pin "8") (pinfunction "O_8") (pintype "output"))
      (node (ref "E5") (pin "2") (pinfunction "A1_2") (pintype "input"))
      (node (ref "U$1") (pin "BH2") (pinfunction "1_BH2") (pintype "bidirectional"))
    )
    (net (code "60") (name "/REG_BUS2") (class "Default")
      (node (ref "E11") (pin "12") (pinfunction "D_12") (pintype "input"))
      (node (ref "E14") (pin "12") (pinfunction "D_12") (pintype "input"))
      (node (ref "E17") (pin "12") (pinfunction "D_12") (pintype "input"))
      (node (ref "E2") (pin "8") (pinfunction "O_8") (pintype "output"))
      (node (ref "E8") (pin "12") (pinfunction "D_12") (pintype "input"))
      (node (ref "U$1") (pin "AD1") (pinfunction "1_AD1") (pintype "bidirectional"))
    )
    (net (code "61") (name "/REG_BUS3") (class "Default")
      (node (ref "E11") (pin "2") (pinfunction "D_2") (pintype "input"))
      (node (ref "E14") (pin "2") (pinfunction "D_2") (pintype "input"))
      (node (ref "E17") (pin "2") (pinfunction "D_2") (pintype "input"))
      (node (ref "E6") (pin "8") (pinfunction "O_8") (pintype "output"))
      (node (ref "E8") (pin "2") (pinfunction "D_2") (pintype "input"))
      (node (ref "U$1") (pin "AV2") (pinfunction "1_AV2") (pintype "bidirectional"))
    )
    (net (code "62") (name "/ROT_LEFT") (class "Default")
      (node (ref "E2") (pin "2") (pinfunction "I5_2") (pintype "input"))
      (node (ref "E6") (pin "3") (pinfunction "I6_3") (pintype "input"))
      (node (ref "U$1") (pin "AF1") (pinfunction "1_AF1") (pintype "bidirectional"))
    )
    (net (code "63") (name "/ROT_RIGHT") (class "Default")
      (node (ref "E2") (pin "1") (pinfunction "I4_1") (pintype "input"))
      (node (ref "E6") (pin "13") (pinfunction "I3_13") (pintype "input"))
      (node (ref "U$1") (pin "AE1") (pinfunction "1_AE1") (pintype "bidirectional"))
    )
    (net (code "64") (name "/RSW2") (class "Default")
      (node (ref "E1") (pin "4") (pinfunction "I1_4") (pintype "input"))
      (node (ref "U$1") (pin "AE2") (pinfunction "1_AE2") (pintype "bidirectional"))
    )
    (net (code "65") (name "/RSW3") (class "Default")
      (node (ref "E20") (pin "4") (pinfunction "I1_4") (pintype "input"))
      (node (ref "U$1") (pin "BM1") (pinfunction "1_BM1") (pintype "bidirectional"))
    )
    (net (code "66") (name "/RS_MSC2") (class "Default")
      (node (ref "E1") (pin "2") (pinfunction "I5_2") (pintype "input"))
      (node (ref "E1") (pin "3") (pinfunction "I6_3") (pintype "input"))
      (node (ref "U$1") (pin "AF2") (pinfunction "1_AF2") (pintype "bidirectional"))
    )
    (net (code "67") (name "/RS_MSC3") (class "Default")
      (node (ref "E20") (pin "2") (pinfunction "I5_2") (pintype "input"))
      (node (ref "E20") (pin "3") (pinfunction "I6_3") (pintype "input"))
      (node (ref "U$1") (pin "BN1") (pinfunction "1_BN1") (pintype "bidirectional"))
    )
    (net (code "68") (name "GND") (class "Default")
      (node (ref "C1") (pin "2") (pinfunction "2_2") (pintype "passive"))
      (node (ref "C10") (pin "2") (pinfunction "2_2") (pintype "passive"))
      (node (ref "C11") (pin "2") (pinfunction "2_2") (pintype "passive"))
      (node (ref "C12") (pin "2") (pinfunction "2_2") (pintype "passive"))
      (node (ref "C13") (pin "2") (pinfunction "2_2") (pintype "passive"))
      (node (ref "C14") (pin "2") (pinfunction "2_2") (pintype "passive"))
      (node (ref "C15") (pin "2") (pinfunction "2_2") (pintype "passive"))
      (node (ref "C16") (pin "2") (pinfunction "2_2") (pintype "passive"))
      (node (ref "C17") (pin "2") (pinfunction "2_2") (pintype "passive"))
      (node (ref "C18") (pin "2") (pinfunction "2_2") (pintype "passive"))
      (node (ref "C19") (pin "2") (pinfunction "2_2") (pintype "passive"))
      (node (ref "C2") (pin "2") (pinfunction "2_2") (pintype "passive"))
      (node (ref "C20") (pin "2") (pinfunction "2_2") (pintype "passive"))
      (node (ref "C21") (pin "2") (pinfunction "2_2") (pintype "passive"))
      (node (ref "C3") (pin "2") (pinfunction "2_2") (pintype "passive"))
      (node (ref "C4") (pin "2") (pinfunction "2_2") (pintype "passive"))
      (node (ref "C5") (pin "2") (pinfunction "2_2") (pintype "passive"))
      (node (ref "C6") (pin "2") (pinfunction "2_2") (pintype "passive"))
      (node (ref "C7") (pin "2") (pinfunction "2_2") (pintype "passive"))
      (node (ref "C8") (pin "2") (pinfunction "2_2") (pintype "passive"))
      (node (ref "C9") (pin "2") (pinfunction "2_2") (pintype "passive"))
      (node (ref "U$1") (pin "AC2") (pinfunction "1_AC2") (pintype "bidirectional"))
      (node (ref "U$1") (pin "AT1") (pinfunction "1_AT1") (pintype "bidirectional"))
      (node (ref "U$1") (pin "BC2") (pinfunction "1_BC2") (pintype "bidirectional"))
      (node (ref "U$1") (pin "BT1") (pinfunction "1_BT1") (pintype "bidirectional"))
    )
    (net (code "69") (name "Net-(E1A-I9)") (class "Default")
      (node (ref "E1") (pin "12") (pinfunction "I9_12") (pintype "passive"))
      (node (ref "E4") (pin "12") (pinfunction "I9_12") (pintype "passive"))
    )
    (net (code "70") (name "Net-(E1A-I10)") (class "Default")
      (node (ref "E1") (pin "11") (pinfunction "I10_11") (pintype "passive"))
      (node (ref "E4") (pin "11") (pinfunction "I10_11") (pintype "passive"))
    )
    (net (code "71") (name "Net-(E2A-I8)") (class "Default")
      (node (ref "E2") (pin "9") (pinfunction "I8_9") (pintype "input"))
      (node (ref "E3") (pin "9") (pinfunction "I8_9") (pintype "input"))
      (node (ref "E9") (pin "11") (pinfunction "O_11") (pintype "output"))
    )
    (net (code "72") (name "Net-(E3A-I1)") (class "Default")
      (node (ref "E3") (pin "4") (pinfunction "I1_4") (pintype "input"))
      (node (ref "E6") (pin "5") (pinfunction "I2_5") (pintype "input"))
      (node (ref "E9") (pin "8") (pinfunction "O_8") (pintype "output"))
    )
    (net (code "73") (name "Net-(E10A-X)") (class "Default")
      (node (ref "E10") (pin "11") (pinfunction "X_11") (pintype "output"))
      (node (ref "E13") (pin "11") (pinfunction "X_11") (pintype "output"))
      (node (ref "E7") (pin "11") (pinfunction "I10_11") (pintype "passive"))
    )
    (net (code "74") (name "Net-(E10A-~{X})") (class "Default")
      (node (ref "E10") (pin "12") (pinfunction "~{X}_12") (pintype "output"))
      (node (ref "E13") (pin "12") (pinfunction "~{X}_12") (pintype "output"))
      (node (ref "E7") (pin "12") (pinfunction "I9_12") (pintype "passive"))
    )
    (net (code "75") (name "Net-(E10B-X)") (class "Default")
      (node (ref "E10") (pin "10") (pinfunction "X_10") (pintype "output"))
      (node (ref "E13") (pin "10") (pinfunction "X_10") (pintype "output"))
      (node (ref "E16") (pin "11") (pinfunction "I10_11") (pintype "passive"))
    )
    (net (code "76") (name "Net-(E10B-~{X})") (class "Default")
      (node (ref "E10") (pin "9") (pinfunction "~{X}_9") (pintype "output"))
      (node (ref "E13") (pin "9") (pinfunction "~{X}_9") (pintype "output"))
      (node (ref "E16") (pin "12") (pinfunction "I9_12") (pintype "passive"))
    )
    (net (code "77") (name "Net-(E12A-I6)") (class "Default")
      (node (ref "E12") (pin "3") (pinfunction "I6_3") (pintype "input"))
      (node (ref "E9") (pin "3") (pinfunction "O_3") (pintype "output"))
    )
    (net (code "78") (name "Net-(E12A-I8)") (class "Default")
      (node (ref "E12") (pin "9") (pinfunction "I8_9") (pintype "input"))
      (node (ref "E9") (pin "6") (pinfunction "O_6") (pintype "output"))
    )
    (net (code "79") (name "Net-(E18A-O)") (class "Default")
      (node (ref "E18") (pin "3") (pinfunction "O_3") (pintype "output"))
      (node (ref "R9") (pin "1") (pinfunction "1_1") (pintype "passive"))
      (node (ref "U$1") (pin "BJ2") (pinfunction "1_BJ2") (pintype "bidirectional"))
    )
    (net (code "80") (name "Net-(E18B-O)") (class "Default")
      (node (ref "E18") (pin "6") (pinfunction "O_6") (pintype "output"))
      (node (ref "R8") (pin "1") (pinfunction "1_1") (pintype "passive"))
      (node (ref "U$1") (pin "BU1") (pinfunction "1_BU1") (pintype "bidirectional"))
    )
    (net (code "81") (name "Net-(E18C-O)") (class "Default")
      (node (ref "E18") (pin "8") (pinfunction "O_8") (pintype "output"))
      (node (ref "R10") (pin "1") (pinfunction "1_1") (pintype "passive"))
      (node (ref "U$1") (pin "BD2") (pinfunction "1_BD2") (pintype "bidirectional"))
    )
    (net (code "82") (name "Net-(E18D-O)") (class "Default")
      (node (ref "E18") (pin "11") (pinfunction "O_11") (pintype "output"))
      (node (ref "R7") (pin "1") (pinfunction "1_1") (pintype "passive"))
      (node (ref "U$1") (pin "AB2") (pinfunction "1_AB2") (pintype "bidirectional"))
    )
    (net (code "83") (name "Net-(E19A-I9)") (class "Default")
      (node (ref "E19") (pin "12") (pinfunction "I9_12") (pintype "passive"))
      (node (ref "E20") (pin "12") (pinfunction "I9_12") (pintype "passive"))
    )
    (net (code "84") (name "Net-(E19A-I10)") (class "Default")
      (node (ref "E19") (pin "11") (pinfunction "I10_11") (pintype "passive"))
      (node (ref "E20") (pin "11") (pinfunction "I10_11") (pintype "passive"))
    )
    (net (code "85") (name "Net-(E21A-O)") (class "Default")
      (node (ref "E21") (pin "3") (pinfunction "O_3") (pintype "output"))
      (node (ref "R14") (pin "1") (pinfunction "1_1") (pintype "passive"))
      (node (ref "U$1") (pin "BR1") (pinfunction "1_BR1") (pintype "bidirectional"))
    )
    (net (code "86") (name "Net-(E21B-O)") (class "Default")
      (node (ref "E21") (pin "6") (pinfunction "O_6") (pintype "output"))
      (node (ref "R13") (pin "1") (pinfunction "1_1") (pintype "passive"))
      (node (ref "U$1") (pin "BR2") (pinfunction "1_BR2") (pintype "bidirectional"))
    )
    (net (code "87") (name "Net-(E21C-O)") (class "Default")
      (node (ref "E21") (pin "8") (pinfunction "O_8") (pintype "output"))
      (node (ref "R11") (pin "1") (pinfunction "1_1") (pintype "passive"))
      (node (ref "U$1") (pin "BF1") (pinfunction "1_BF1") (pintype "bidirectional"))
    )
    (net (code "88") (name "Net-(E21D-O)") (class "Default")
      (node (ref "E21") (pin "11") (pinfunction "O_11") (pintype "output"))
      (node (ref "R12") (pin "1") (pinfunction "1_1") (pintype "passive"))
      (node (ref "U$1") (pin "BS1") (pinfunction "1_BS1") (pintype "bidirectional"))
    )
    (net (code "89") (name "VCC") (class "Default")
      (node (ref "C1") (pin "1") (pinfunction "1_1") (pintype "passive"))
      (node (ref "C10") (pin "1") (pinfunction "1_1") (pintype "passive"))
      (node (ref "C11") (pin "1") (pinfunction "1_1") (pintype "passive"))
      (node (ref "C12") (pin "1") (pinfunction "1_1") (pintype "passive"))
      (node (ref "C13") (pin "1") (pinfunction "1_1") (pintype "passive"))
      (node (ref "C14") (pin "1") (pinfunction "1_1") (pintype "passive"))
      (node (ref "C15") (pin "1") (pinfunction "1_1") (pintype "passive"))
      (node (ref "C16") (pin "1") (pinfunction "1_1") (pintype "passive"))
      (node (ref "C17") (pin "1") (pinfunction "1_1") (pintype "passive"))
      (node (ref "C18") (pin "1") (pinfunction "1_1") (pintype "passive"))
      (node (ref "C19") (pin "1") (pinfunction "1_1") (pintype "passive"))
      (node (ref "C2") (pin "1") (pinfunction "1_1") (pintype "passive"))
      (node (ref "C20") (pin "1") (pinfunction "1_1") (pintype "passive"))
      (node (ref "C21") (pin "1") (pinfunction "1_1") (pintype "passive"))
      (node (ref "C3") (pin "1") (pinfunction "1_1") (pintype "passive"))
      (node (ref "C4") (pin "1") (pinfunction "1_1") (pintype "passive"))
      (node (ref "C5") (pin "1") (pinfunction "1_1") (pintype "passive"))
      (node (ref "C6") (pin "1") (pinfunction "1_1") (pintype "passive"))
      (node (ref "C7") (pin "1") (pinfunction "1_1") (pintype "passive"))
      (node (ref "C8") (pin "1") (pinfunction "1_1") (pintype "passive"))
      (node (ref "C9") (pin "1") (pinfunction "1_1") (pintype "passive"))
      (node (ref "R1") (pin "2") (pinfunction "2_2") (pintype "passive"))
      (node (ref "R10") (pin "2") (pinfunction "2_2") (pintype "passive"))
      (node (ref "R11") (pin "2") (pinfunction "2_2") (pintype "passive"))
      (node (ref "R12") (pin "2") (pinfunction "2_2") (pintype "passive"))
      (node (ref "R13") (pin "2") (pinfunction "2_2") (pintype "passive"))
      (node (ref "R14") (pin "2") (pinfunction "2_2") (pintype "passive"))
      (node (ref "R2") (pin "2") (pinfunction "2_2") (pintype "passive"))
      (node (ref "R3") (pin "2") (pinfunction "2_2") (pintype "passive"))
      (node (ref "R4") (pin "2") (pinfunction "2_2") (pintype "passive"))
      (node (ref "R5") (pin "2") (pinfunction "2_2") (pintype "passive"))
      (node (ref "R6") (pin "2") (pinfunction "2_2") (pintype "passive"))
      (node (ref "R7") (pin "2") (pinfunction "2_2") (pintype "passive"))
      (node (ref "R8") (pin "2") (pinfunction "2_2") (pintype "passive"))
      (node (ref "R9") (pin "2") (pinfunction "2_2") (pintype "passive"))
      (node (ref "U$1") (pin "AA2") (pinfunction "1_AA2") (pintype "bidirectional"))
      (node (ref "U$1") (pin "BA2") (pinfunction "1_BA2") (pintype "bidirectional"))
    )
    (net (code "90") (name "unconnected-(E2A-I9-Pad12)") (class "Default")
      (node (ref "E2") (pin "12") (pinfunction "I9_12") (pintype "passive"))
    )
    (net (code "91") (name "unconnected-(E2A-I10-Pad11)") (class "Default")
      (node (ref "E2") (pin "11") (pinfunction "I10_11") (pintype "passive"))
    )
    (net (code "92") (name "unconnected-(E3A-I9-Pad12)") (class "Default")
      (node (ref "E3") (pin "12") (pinfunction "I9_12") (pintype "passive"))
    )
    (net (code "93") (name "unconnected-(E3A-I10-Pad11)") (class "Default")
      (node (ref "E3") (pin "11") (pinfunction "I10_11") (pintype "passive"))
    )
    (net (code "94") (name "unconnected-(E6A-I9-Pad12)") (class "Default")
      (node (ref "E6") (pin "12") (pinfunction "I9_12") (pintype "passive"))
    )
    (net (code "95") (name "unconnected-(E6A-I10-Pad11)") (class "Default")
      (node (ref "E6") (pin "11") (pinfunction "I10_11") (pintype "passive"))
    )
    (net (code "96") (name "unconnected-(E8A-CLR-Pad1)") (class "Default")
      (node (ref "E8") (pin "1") (pinfunction "CLR_1") (pintype "input"))
    )
    (net (code "97") (name "unconnected-(E8A-PRE-Pad4)") (class "Default")
      (node (ref "E8") (pin "4") (pinfunction "PRE_4") (pintype "input"))
    )
    (net (code "98") (name "unconnected-(E8B-CLR-Pad13)") (class "Default")
      (node (ref "E8") (pin "13") (pinfunction "CLR_13") (pintype "input"))
    )
    (net (code "99") (name "unconnected-(E8B-PRE-Pad10)") (class "Default")
      (node (ref "E8") (pin "10") (pinfunction "PRE_10") (pintype "input"))
    )
    (net (code "100") (name "unconnected-(E11A-CLR-Pad1)") (class "Default")
      (node (ref "E11") (pin "1") (pinfunction "CLR_1") (pintype "input"))
    )
    (net (code "101") (name "unconnected-(E11A-PRE-Pad4)") (class "Default")
      (node (ref "E11") (pin "4") (pinfunction "PRE_4") (pintype "input"))
    )
    (net (code "102") (name "unconnected-(E11B-CLR-Pad13)") (class "Default")
      (node (ref "E11") (pin "13") (pinfunction "CLR_13") (pintype "input"))
    )
    (net (code "103") (name "unconnected-(E11B-PRE-Pad10)") (class "Default")
      (node (ref "E11") (pin "10") (pinfunction "PRE_10") (pintype "input"))
    )
    (net (code "104") (name "unconnected-(E12A-I9-Pad12)") (class "Default")
      (node (ref "E12") (pin "12") (pinfunction "I9_12") (pintype "passive"))
    )
    (net (code "105") (name "unconnected-(E12A-I10-Pad11)") (class "Default")
      (node (ref "E12") (pin "11") (pinfunction "I10_11") (pintype "passive"))
    )
    (net (code "106") (name "unconnected-(E14A-CLR-Pad1)") (class "Default")
      (node (ref "E14") (pin "1") (pinfunction "CLR_1") (pintype "input"))
    )
    (net (code "107") (name "unconnected-(E14A-PRE-Pad4)") (class "Default")
      (node (ref "E14") (pin "4") (pinfunction "PRE_4") (pintype "input"))
    )
    (net (code "108") (name "unconnected-(E14B-CLR-Pad13)") (class "Default")
      (node (ref "E14") (pin "13") (pinfunction "CLR_13") (pintype "input"))
    )
    (net (code "109") (name "unconnected-(E14B-PRE-Pad10)") (class "Default")
      (node (ref "E14") (pin "10") (pinfunction "PRE_10") (pintype "input"))
    )
    (net (code "110") (name "unconnected-(E15A-I9-Pad12)") (class "Default")
      (node (ref "E15") (pin "12") (pinfunction "I9_12") (pintype "passive"))
    )
    (net (code "111") (name "unconnected-(E15A-I10-Pad11)") (class "Default")
      (node (ref "E15") (pin "11") (pinfunction "I10_11") (pintype "passive"))
    )
    (net (code "112") (name "unconnected-(E17A-CLR-Pad1)") (class "Default")
      (node (ref "E17") (pin "1") (pinfunction "CLR_1") (pintype "input"))
    )
    (net (code "113") (name "unconnected-(E17A-PRE-Pad4)") (class "Default")
      (node (ref "E17") (pin "4") (pinfunction "PRE_4") (pintype "input"))
    )
    (net (code "114") (name "unconnected-(E17B-CLR-Pad13)") (class "Default")
      (node (ref "E17") (pin "13") (pinfunction "CLR_13") (pintype "input"))
    )
    (net (code "115") (name "unconnected-(E17B-PRE-Pad10)") (class "Default")
      (node (ref "E17") (pin "10") (pinfunction "PRE_10") (pintype "input"))
    )
  )
)
